# 05_USB7002-PartB.net
KiCad netlist of a schematic drawn in Altium Designer
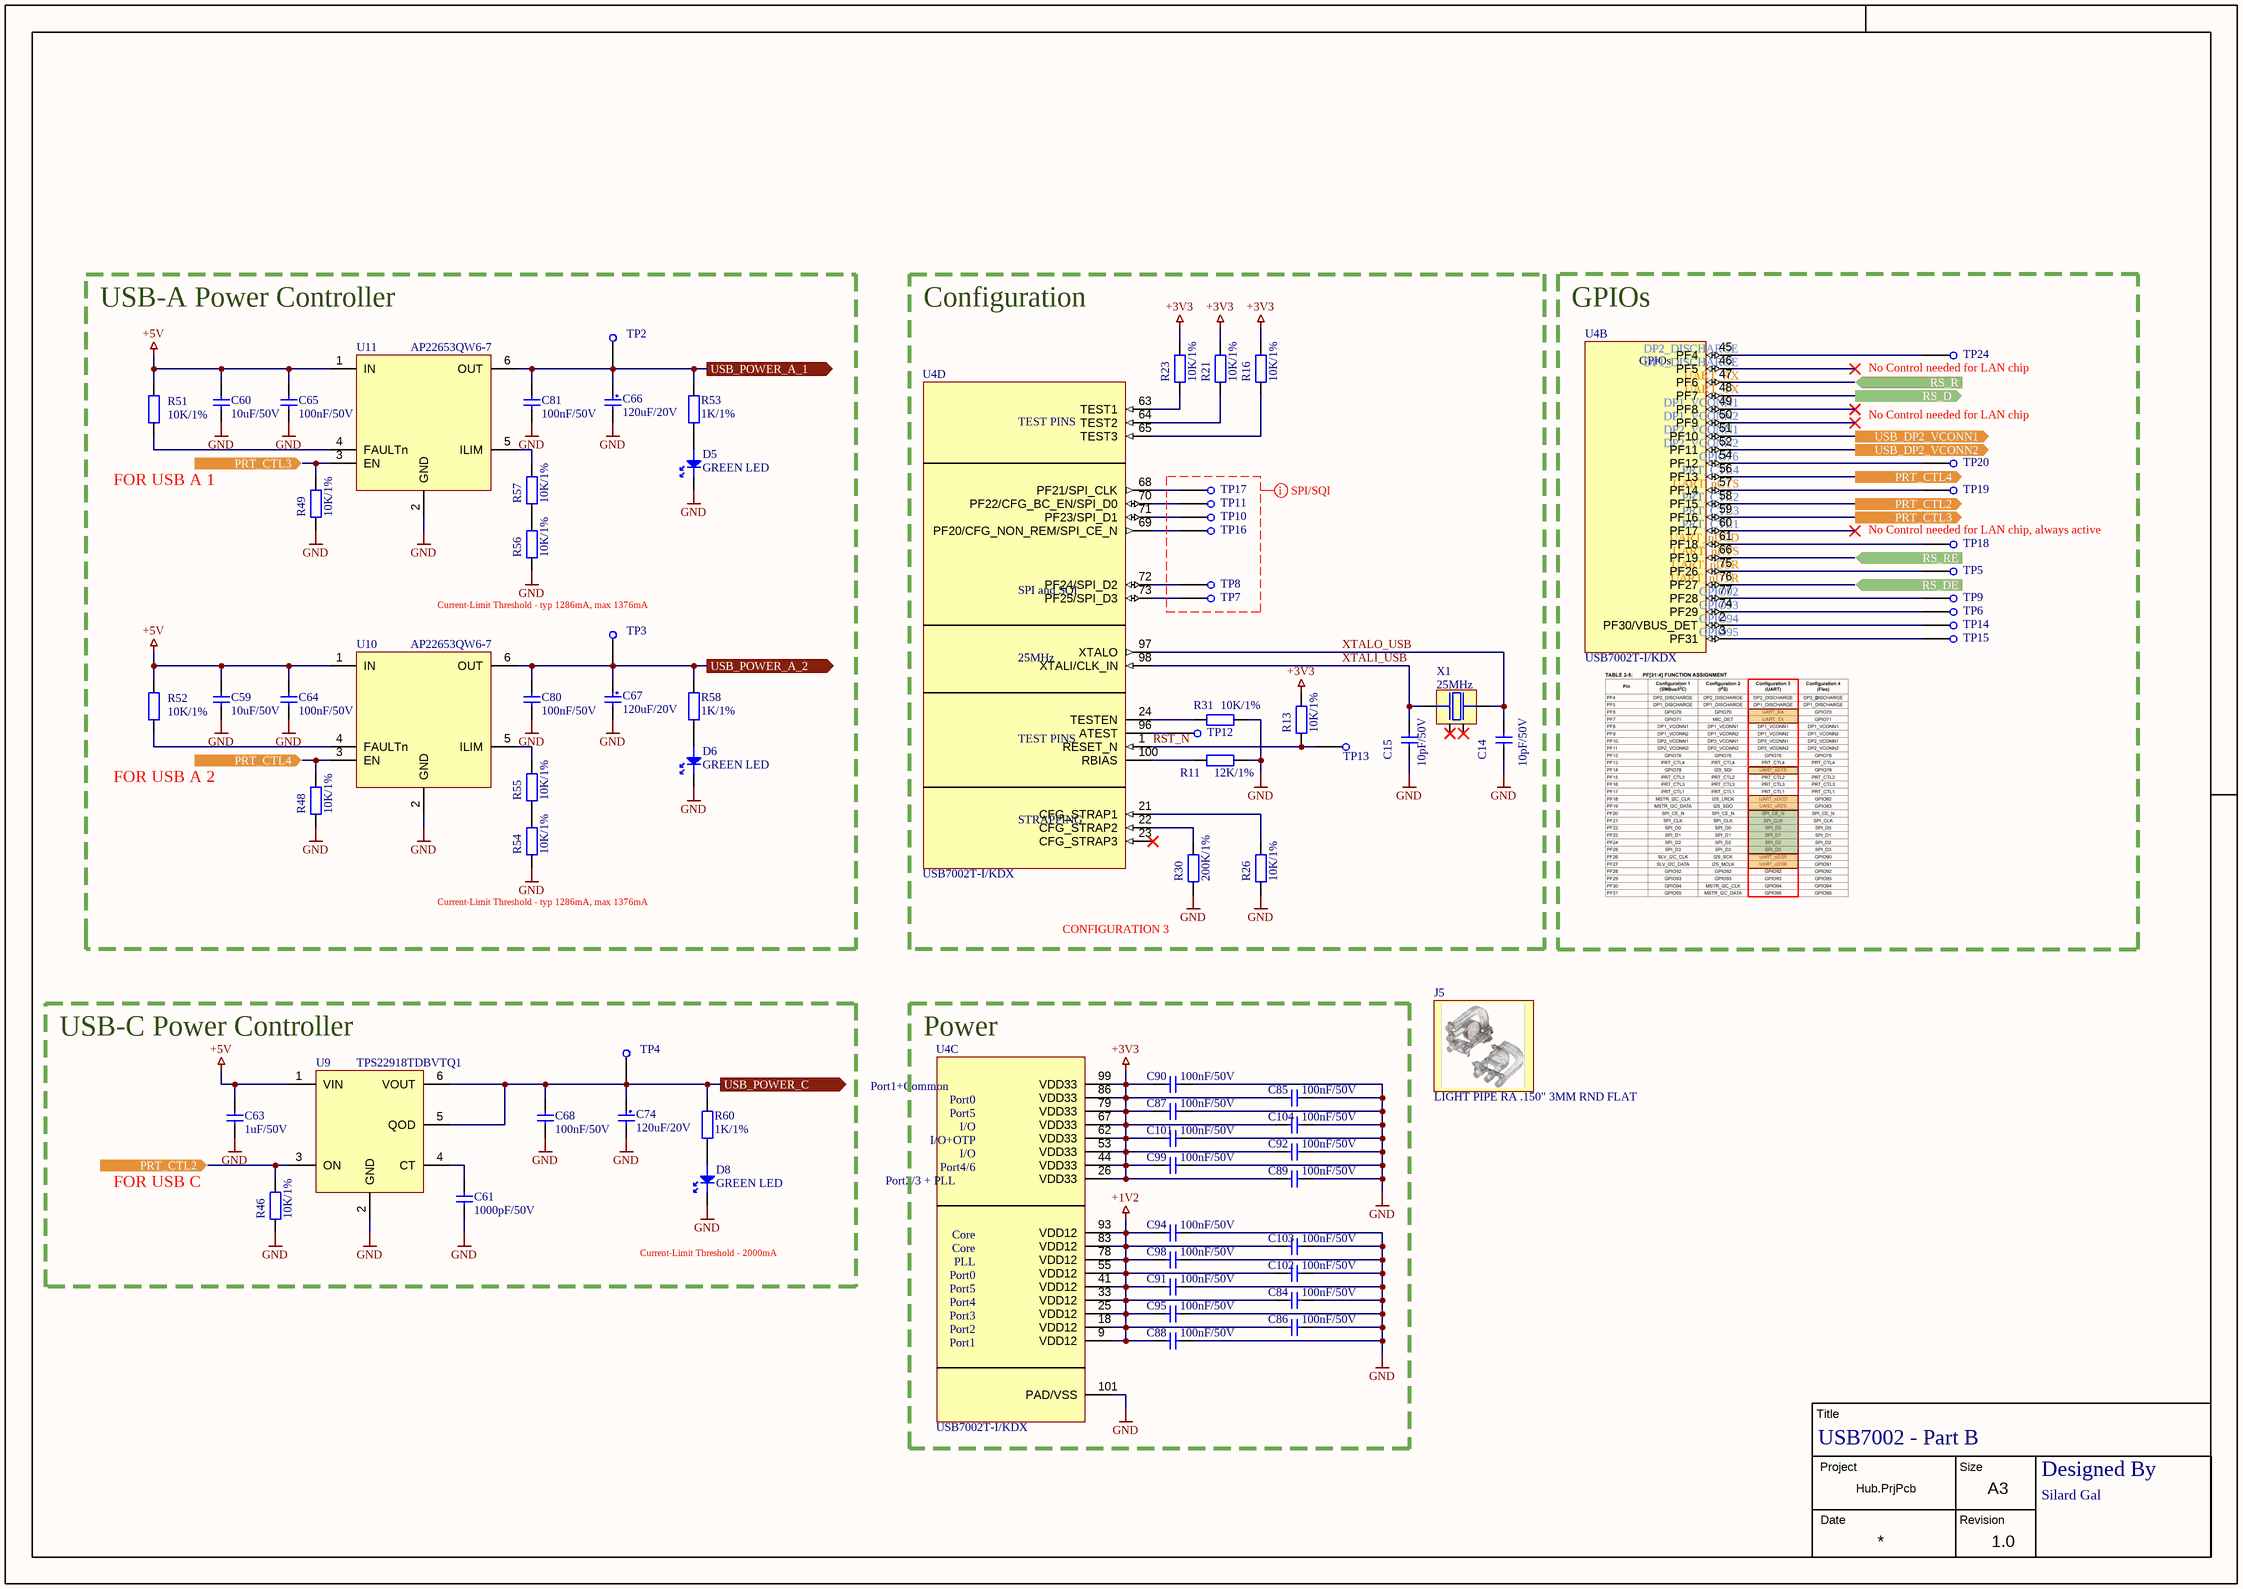
[diagram p0: 05 USB7002-PartB.SchDoc]

(export (version "E")
  (design (tool "Eeschema 10.0.6"))
  (components
    (comp (ref "C14")
      (value "10pF/50V")
      (footprint "CAPC1005X06N")
      (description "10 pF ±5% 50V Ceramic Capacitor C0G, NP0 0402 (1005 Metric)")
      (fields
        (field (name "MANUFACTURER") "Murata Electronics")
        (field (name "MFR_PART_NUMBER") "GCM1555C1H100JA16D")
      )
      (libsource (lib "altium_symbol") (part "GCM1555C1H100JA16D"))
    )
    (comp (ref "C15")
      (value "10pF/50V")
      (footprint "CAPC1005X06N")
      (description "10 pF ±5% 50V Ceramic Capacitor C0G, NP0 0402 (1005 Metric)")
      (fields
        (field (name "MANUFACTURER") "Murata Electronics")
        (field (name "MFR_PART_NUMBER") "GCM1555C1H100JA16D")
      )
      (libsource (lib "altium_symbol") (part "GCM1555C1H100JA16D"))
    )
    (comp (ref "C59")
      (value "10uF/50V")
      (footprint "CAPC3216X18N")
      (description "10 µF ±20% 50V Ceramic Capacitor X5R 1206 (3216 Metric)")
      (fields
        (field (name "MANUFACTURER") "Murata Electronics")
        (field (name "MFR_PART_NUMBER") "GRT31CR61H106ME01L")
      )
      (libsource (lib "altium_symbol") (part "GRT31CR61H106ME01L"))
    )
    (comp (ref "C60")
      (value "10uF/50V")
      (footprint "CAPC3216X18N")
      (description "10 µF ±20% 50V Ceramic Capacitor X5R 1206 (3216 Metric)")
      (fields
        (field (name "MANUFACTURER") "Murata Electronics")
        (field (name "MFR_PART_NUMBER") "GRT31CR61H106ME01L")
      )
      (libsource (lib "altium_symbol") (part "GRT31CR61H106ME01L"))
    )
    (comp (ref "C61")
      (value "1000pF/50V")
      (footprint "CAPC1005X06N")
      (description "1000 pF ±10% 50V Ceramic Capacitor X7R 0402 (1005 Metric)")
      (fields (field (name "MANUFACTURER") "KEMET") (field (name "MFR_PART_NUMBER") "C0402C102K5RECAUTO"))
      (libsource (lib "altium_symbol") (part "C0402C102K5RECAUTO"))
    )
    (comp (ref "C63")
      (value "1uF/50V")
      (footprint "INDC1608X10N")
      (description "1 µF ±10% 50V Ceramic Capacitor X5R 0603 (1608 Metric)")
      (fields
        (field (name "MANUFACTURER") "Murata Electronics")
        (field (name "MFR_PART_NUMBER") "GRT188R61H105KE13D")
      )
      (libsource (lib "altium_symbol") (part "GRT188R61H105KE13D"))
    )
    (comp (ref "C64")
      (value "100nF/50V")
      (footprint "CAPC1005X06N")
      (description "0.1 µF ±10% 50V Ceramic Capacitor X7R 0402 (1005 Metric)")
      (fields
        (field (name "MANUFACTURER") "Murata Electronics")
        (field (name "MFR_PART_NUMBER") "GCM155R71H104KE02J")
      )
      (libsource (lib "altium_symbol") (part "GCM155R71H104KE02J"))
    )
    (comp (ref "C65")
      (value "100nF/50V")
      (footprint "CAPC1005X06N")
      (description "0.1 µF ±10% 50V Ceramic Capacitor X7R 0402 (1005 Metric)")
      (fields
        (field (name "MANUFACTURER") "Murata Electronics")
        (field (name "MFR_PART_NUMBER") "GCM155R71H104KE02J")
      )
      (libsource (lib "altium_symbol") (part "GCM155R71H104KE02J"))
    )
    (comp (ref "C66")
      (value "120uF/20V")
      (footprint "CAPAE7366X60M")
      (description "120 µF 20 V Aluminum - Polymer Capacitors Radial, Can - SMD 34mOhm 2000 Hrs @ 125°C")
      (fields (field (name "MANUFACTURER") "KEMET") (field (name "MFR_PART_NUMBER") "A768EB127M1DLAS034"))
      (libsource (lib "altium_symbol") (part "A768EB127M1DLAS034"))
    )
    (comp (ref "C67")
      (value "120uF/20V")
      (footprint "CAPAE7366X60M")
      (description "120 µF 20 V Aluminum - Polymer Capacitors Radial, Can - SMD 34mOhm 2000 Hrs @ 125°C")
      (fields (field (name "MANUFACTURER") "KEMET") (field (name "MFR_PART_NUMBER") "A768EB127M1DLAS034"))
      (libsource (lib "altium_symbol") (part "A768EB127M1DLAS034"))
    )
    (comp (ref "C68")
      (value "100nF/50V")
      (footprint "CAPC1005X06N")
      (description "0.1 µF ±10% 50V Ceramic Capacitor X7R 0402 (1005 Metric)")
      (fields
        (field (name "MANUFACTURER") "Murata Electronics")
        (field (name "MFR_PART_NUMBER") "GCM155R71H104KE02J")
      )
      (libsource (lib "altium_symbol") (part "GCM155R71H104KE02J"))
    )
    (comp (ref "C74")
      (value "120uF/20V")
      (footprint "CAPAE7366X60M")
      (description "120 µF 20 V Aluminum - Polymer Capacitors Radial, Can - SMD 34mOhm 2000 Hrs @ 125°C")
      (fields (field (name "MANUFACTURER") "KEMET") (field (name "MFR_PART_NUMBER") "A768EB127M1DLAS034"))
      (libsource (lib "altium_symbol") (part "A768EB127M1DLAS034"))
    )
    (comp (ref "C80")
      (value "100nF/50V")
      (footprint "CAPC1005X06N")
      (description "0.1 µF ±10% 50V Ceramic Capacitor X7R 0402 (1005 Metric)")
      (fields
        (field (name "MANUFACTURER") "Murata Electronics")
        (field (name "MFR_PART_NUMBER") "GCM155R71H104KE02J")
      )
      (libsource (lib "altium_symbol") (part "GCM155R71H104KE02J"))
    )
    (comp (ref "C81")
      (value "100nF/50V")
      (footprint "CAPC1005X06N")
      (description "0.1 µF ±10% 50V Ceramic Capacitor X7R 0402 (1005 Metric)")
      (fields
        (field (name "MANUFACTURER") "Murata Electronics")
        (field (name "MFR_PART_NUMBER") "GCM155R71H104KE02J")
      )
      (libsource (lib "altium_symbol") (part "GCM155R71H104KE02J"))
    )
    (comp (ref "C84")
      (value "100nF/50V")
      (footprint "CAPC1005X06N")
      (description "0.1 µF ±10% 50V Ceramic Capacitor X7R 0402 (1005 Metric)")
      (fields
        (field (name "MANUFACTURER") "Murata Electronics")
        (field (name "MFR_PART_NUMBER") "GCM155R71H104KE02J")
      )
      (libsource (lib "altium_symbol") (part "GCM155R71H104KE02J"))
    )
    (comp (ref "C85")
      (value "100nF/50V")
      (footprint "CAPC1005X06N")
      (description "0.1 µF ±10% 50V Ceramic Capacitor X7R 0402 (1005 Metric)")
      (fields
        (field (name "MANUFACTURER") "Murata Electronics")
        (field (name "MFR_PART_NUMBER") "GCM155R71H104KE02J")
      )
      (libsource (lib "altium_symbol") (part "GCM155R71H104KE02J"))
    )
    (comp (ref "C86")
      (value "100nF/50V")
      (footprint "CAPC1005X06N")
      (description "0.1 µF ±10% 50V Ceramic Capacitor X7R 0402 (1005 Metric)")
      (fields
        (field (name "MANUFACTURER") "Murata Electronics")
        (field (name "MFR_PART_NUMBER") "GCM155R71H104KE02J")
      )
      (libsource (lib "altium_symbol") (part "GCM155R71H104KE02J"))
    )
    (comp (ref "C87")
      (value "100nF/50V")
      (footprint "CAPC1005X06N")
      (description "0.1 µF ±10% 50V Ceramic Capacitor X7R 0402 (1005 Metric)")
      (fields
        (field (name "MANUFACTURER") "Murata Electronics")
        (field (name "MFR_PART_NUMBER") "GCM155R71H104KE02J")
      )
      (libsource (lib "altium_symbol") (part "GCM155R71H104KE02J"))
    )
    (comp (ref "C88")
      (value "100nF/50V")
      (footprint "CAPC1005X06N")
      (description "0.1 µF ±10% 50V Ceramic Capacitor X7R 0402 (1005 Metric)")
      (fields
        (field (name "MANUFACTURER") "Murata Electronics")
        (field (name "MFR_PART_NUMBER") "GCM155R71H104KE02J")
      )
      (libsource (lib "altium_symbol") (part "GCM155R71H104KE02J"))
    )
    (comp (ref "C89")
      (value "100nF/50V")
      (footprint "CAPC1005X06N")
      (description "0.1 µF ±10% 50V Ceramic Capacitor X7R 0402 (1005 Metric)")
      (fields
        (field (name "MANUFACTURER") "Murata Electronics")
        (field (name "MFR_PART_NUMBER") "GCM155R71H104KE02J")
      )
      (libsource (lib "altium_symbol") (part "GCM155R71H104KE02J"))
    )
    (comp (ref "C90")
      (value "100nF/50V")
      (footprint "CAPC1005X06N")
      (description "0.1 µF ±10% 50V Ceramic Capacitor X7R 0402 (1005 Metric)")
      (fields
        (field (name "MANUFACTURER") "Murata Electronics")
        (field (name "MFR_PART_NUMBER") "GCM155R71H104KE02J")
      )
      (libsource (lib "altium_symbol") (part "GCM155R71H104KE02J"))
    )
    (comp (ref "C91")
      (value "100nF/50V")
      (footprint "CAPC1005X06N")
      (description "0.1 µF ±10% 50V Ceramic Capacitor X7R 0402 (1005 Metric)")
      (fields
        (field (name "MANUFACTURER") "Murata Electronics")
        (field (name "MFR_PART_NUMBER") "GCM155R71H104KE02J")
      )
      (libsource (lib "altium_symbol") (part "GCM155R71H104KE02J"))
    )
    (comp (ref "C92")
      (value "100nF/50V")
      (footprint "CAPC1005X06N")
      (description "0.1 µF ±10% 50V Ceramic Capacitor X7R 0402 (1005 Metric)")
      (fields
        (field (name "MANUFACTURER") "Murata Electronics")
        (field (name "MFR_PART_NUMBER") "GCM155R71H104KE02J")
      )
      (libsource (lib "altium_symbol") (part "GCM155R71H104KE02J"))
    )
    (comp (ref "C94")
      (value "100nF/50V")
      (footprint "CAPC1005X06N")
      (description "0.1 µF ±10% 50V Ceramic Capacitor X7R 0402 (1005 Metric)")
      (fields
        (field (name "MANUFACTURER") "Murata Electronics")
        (field (name "MFR_PART_NUMBER") "GCM155R71H104KE02J")
      )
      (libsource (lib "altium_symbol") (part "GCM155R71H104KE02J"))
    )
    (comp (ref "C95")
      (value "100nF/50V")
      (footprint "CAPC1005X06N")
      (description "0.1 µF ±10% 50V Ceramic Capacitor X7R 0402 (1005 Metric)")
      (fields
        (field (name "MANUFACTURER") "Murata Electronics")
        (field (name "MFR_PART_NUMBER") "GCM155R71H104KE02J")
      )
      (libsource (lib "altium_symbol") (part "GCM155R71H104KE02J"))
    )
    (comp (ref "C98")
      (value "100nF/50V")
      (footprint "CAPC1005X06N")
      (description "0.1 µF ±10% 50V Ceramic Capacitor X7R 0402 (1005 Metric)")
      (fields
        (field (name "MANUFACTURER") "Murata Electronics")
        (field (name "MFR_PART_NUMBER") "GCM155R71H104KE02J")
      )
      (libsource (lib "altium_symbol") (part "GCM155R71H104KE02J"))
    )
    (comp (ref "C99")
      (value "100nF/50V")
      (footprint "CAPC1005X06N")
      (description "0.1 µF ±10% 50V Ceramic Capacitor X7R 0402 (1005 Metric)")
      (fields
        (field (name "MANUFACTURER") "Murata Electronics")
        (field (name "MFR_PART_NUMBER") "GCM155R71H104KE02J")
      )
      (libsource (lib "altium_symbol") (part "GCM155R71H104KE02J"))
    )
    (comp (ref "C101")
      (value "100nF/50V")
      (footprint "CAPC1005X06N")
      (description "0.1 µF ±10% 50V Ceramic Capacitor X7R 0402 (1005 Metric)")
      (fields
        (field (name "MANUFACTURER") "Murata Electronics")
        (field (name "MFR_PART_NUMBER") "GCM155R71H104KE02J")
      )
      (libsource (lib "altium_symbol") (part "GCM155R71H104KE02J"))
    )
    (comp (ref "C102")
      (value "100nF/50V")
      (footprint "CAPC1005X06N")
      (description "0.1 µF ±10% 50V Ceramic Capacitor X7R 0402 (1005 Metric)")
      (fields
        (field (name "MANUFACTURER") "Murata Electronics")
        (field (name "MFR_PART_NUMBER") "GCM155R71H104KE02J")
      )
      (libsource (lib "altium_symbol") (part "GCM155R71H104KE02J"))
    )
    (comp (ref "C103")
      (value "100nF/50V")
      (footprint "CAPC1005X06N")
      (description "0.1 µF ±10% 50V Ceramic Capacitor X7R 0402 (1005 Metric)")
      (fields
        (field (name "MANUFACTURER") "Murata Electronics")
        (field (name "MFR_PART_NUMBER") "GCM155R71H104KE02J")
      )
      (libsource (lib "altium_symbol") (part "GCM155R71H104KE02J"))
    )
    (comp (ref "C104")
      (value "100nF/50V")
      (footprint "CAPC1005X06N")
      (description "0.1 µF ±10% 50V Ceramic Capacitor X7R 0402 (1005 Metric)")
      (fields
        (field (name "MANUFACTURER") "Murata Electronics")
        (field (name "MFR_PART_NUMBER") "GCM155R71H104KE02J")
      )
      (libsource (lib "altium_symbol") (part "GCM155R71H104KE02J"))
    )
    (comp (ref "D5")
      (value "GREEN LED")
      (footprint "DIOC1608X06L")
      (description "White 0402 Light Emitting Diodes (LED) RoHS")
      (fields (field (name "MANUFACTURER") "Lite-On Inc.") (field (name "MFR_PART_NUMBER") "LTST-C191KGKT"))
      (libsource (lib "altium_symbol") (part "LTST-C191KGKT"))
    )
    (comp (ref "D6")
      (value "GREEN LED")
      (footprint "DIOC1608X06L")
      (description "White 0402 Light Emitting Diodes (LED) RoHS")
      (fields (field (name "MANUFACTURER") "Lite-On Inc.") (field (name "MFR_PART_NUMBER") "LTST-C191KGKT"))
      (libsource (lib "altium_symbol") (part "LTST-C191KGKT"))
    )
    (comp (ref "D8")
      (value "GREEN LED")
      (footprint "DIOC1608X06L")
      (description "White 0402 Light Emitting Diodes (LED) RoHS")
      (fields (field (name "MANUFACTURER") "Lite-On Inc.") (field (name "MFR_PART_NUMBER") "LTST-C191KGKT"))
      (libsource (lib "altium_symbol") (part "LTST-C191KGKT"))
    )
    (comp (ref "J5")
      (value "LIGHT PIPE RA .150\" 3MM RND FLAT")
      (footprint "5151064F")
      (description "Light Pipe 3 High Clear Rigid Board Mount, Press Fit, Right Angle")
      (fields (field (name "MANUFACTURER") "Dialight") (field (name "MFR_PART_NUMBER") "5151064F"))
      (libsource (lib "altium_symbol") (part "5151064F"))
    )
    (comp (ref "R11")
      (value "12K/1%")
      (footprint "RESC1005X04N")
      (description "12 kOhms ±1% 0.1W, 1/10W Chip Resistor 0402 (1005 Metric) Automotive AEC-Q200 Thick Film")
      (fields
        (field (name "MANUFACTURER") "Panasonic Electronic Components")
        (field (name "MFR_PART_NUMBER") "ERJ-2RKF1202X")
      )
      (libsource (lib "altium_symbol") (part "ERJ-2RKF1202X"))
    )
    (comp (ref "R13")
      (value "10K/1%")
      (footprint "RESC1005X04N")
      (description "10 kOhms ±1% 0.063W, 1/16W Chip Resistor 0402 (1005 Metric) Automotive AEC-Q200 Thick Film")
      (fields
        (field (name "MANUFACTURER") "Stackpole Electronics Inc")
        (field (name "MFR_PART_NUMBER") "RMCF0402FT10K0")
      )
      (libsource (lib "altium_symbol") (part "RMCF0402FT10K0"))
    )
    (comp (ref "R16")
      (value "10K/1%")
      (footprint "RESC1005X04N")
      (description "10 kOhms ±1% 0.063W, 1/16W Chip Resistor 0402 (1005 Metric) Automotive AEC-Q200 Thick Film")
      (fields
        (field (name "MANUFACTURER") "Stackpole Electronics Inc")
        (field (name "MFR_PART_NUMBER") "RMCF0402FT10K0")
      )
      (libsource (lib "altium_symbol") (part "RMCF0402FT10K0"))
    )
    (comp (ref "R21")
      (value "10K/1%")
      (footprint "RESC1005X04N")
      (description "10 kOhms ±1% 0.063W, 1/16W Chip Resistor 0402 (1005 Metric) Automotive AEC-Q200 Thick Film")
      (fields
        (field (name "MANUFACTURER") "Stackpole Electronics Inc")
        (field (name "MFR_PART_NUMBER") "RMCF0402FT10K0")
      )
      (libsource (lib "altium_symbol") (part "RMCF0402FT10K0"))
    )
    (comp (ref "R23")
      (value "10K/1%")
      (footprint "RESC1005X04N")
      (description "10 kOhms ±1% 0.063W, 1/16W Chip Resistor 0402 (1005 Metric) Automotive AEC-Q200 Thick Film")
      (fields
        (field (name "MANUFACTURER") "Stackpole Electronics Inc")
        (field (name "MFR_PART_NUMBER") "RMCF0402FT10K0")
      )
      (libsource (lib "altium_symbol") (part "RMCF0402FT10K0"))
    )
    (comp (ref "R26")
      (value "10K/1%")
      (footprint "RESC1005X04N")
      (description "10 kOhms ±1% 0.063W, 1/16W Chip Resistor 0402 (1005 Metric) Automotive AEC-Q200 Thick Film")
      (fields
        (field (name "MANUFACTURER") "Stackpole Electronics Inc")
        (field (name "MFR_PART_NUMBER") "RMCF0402FT10K0")
      )
      (libsource (lib "altium_symbol") (part "RMCF0402FT10K0"))
    )
    (comp (ref "R30")
      (value "200K/1%")
      (footprint "RESC1005X04N")
      (description "200 kOhms ±1% 0.063W, 1/16W Chip Resistor 0402 (1005 Metric) Automotive AEC-Q200 Thick Film")
      (fields
        (field (name "MANUFACTURER") "Stackpole Electronics Inc")
        (field (name "MFR_PART_NUMBER") "RMCF0402FT200K")
      )
      (libsource (lib "altium_symbol") (part "RMCF0402FT200K"))
    )
    (comp (ref "R31")
      (value "10K/1%")
      (footprint "RESC1005X04N")
      (description "10 kOhms ±1% 0.063W, 1/16W Chip Resistor 0402 (1005 Metric) Automotive AEC-Q200 Thick Film")
      (fields
        (field (name "MANUFACTURER") "Stackpole Electronics Inc")
        (field (name "MFR_PART_NUMBER") "RMCF0402FT10K0")
      )
      (libsource (lib "altium_symbol") (part "RMCF0402FT10K0"))
    )
    (comp (ref "R46")
      (value "10K/1%")
      (footprint "RESC1005X04N")
      (description "10 kOhms ±1% 0.063W, 1/16W Chip Resistor 0402 (1005 Metric) Automotive AEC-Q200 Thick Film")
      (fields
        (field (name "MANUFACTURER") "Stackpole Electronics Inc")
        (field (name "MFR_PART_NUMBER") "RMCF0402FT10K0")
      )
      (libsource (lib "altium_symbol") (part "RMCF0402FT10K0"))
    )
    (comp (ref "R48")
      (value "10K/1%")
      (footprint "RESC1005X04N")
      (description "10 kOhms ±1% 0.063W, 1/16W Chip Resistor 0402 (1005 Metric) Automotive AEC-Q200 Thick Film")
      (fields
        (field (name "MANUFACTURER") "Stackpole Electronics Inc")
        (field (name "MFR_PART_NUMBER") "RMCF0402FT10K0")
      )
      (libsource (lib "altium_symbol") (part "RMCF0402FT10K0"))
    )
    (comp (ref "R49")
      (value "10K/1%")
      (footprint "RESC1005X04N")
      (description "10 kOhms ±1% 0.063W, 1/16W Chip Resistor 0402 (1005 Metric) Automotive AEC-Q200 Thick Film")
      (fields
        (field (name "MANUFACTURER") "Stackpole Electronics Inc")
        (field (name "MFR_PART_NUMBER") "RMCF0402FT10K0")
      )
      (libsource (lib "altium_symbol") (part "RMCF0402FT10K0"))
    )
    (comp (ref "R51")
      (value "10K/1%")
      (footprint "RESC1005X04N")
      (description "10 kOhms ±1% 0.063W, 1/16W Chip Resistor 0402 (1005 Metric) Automotive AEC-Q200 Thick Film")
      (fields
        (field (name "MANUFACTURER") "Stackpole Electronics Inc")
        (field (name "MFR_PART_NUMBER") "RMCF0402FT10K0")
      )
      (libsource (lib "altium_symbol") (part "RMCF0402FT10K0"))
    )
    (comp (ref "R52")
      (value "10K/1%")
      (footprint "RESC1005X04N")
      (description "10 kOhms ±1% 0.063W, 1/16W Chip Resistor 0402 (1005 Metric) Automotive AEC-Q200 Thick Film")
      (fields
        (field (name "MANUFACTURER") "Stackpole Electronics Inc")
        (field (name "MFR_PART_NUMBER") "RMCF0402FT10K0")
      )
      (libsource (lib "altium_symbol") (part "RMCF0402FT10K0"))
    )
    (comp (ref "R53")
      (value "1K/1%")
      (footprint "RESC1005X04N")
      (description "1 kOhms ±1% 0.063W, 1/16W Chip Resistor 0402 (1005 Metric) Automotive AEC-Q200 Thick Film")
      (fields
        (field (name "MANUFACTURER") "Stackpole Electronics Inc")
        (field (name "MFR_PART_NUMBER") "RMCF0402FT1K00")
      )
      (libsource (lib "altium_symbol") (part "RMCF0402FT1K00"))
    )
    (comp (ref "R54")
      (value "10K/1%")
      (footprint "RESC1005X04N")
      (description "10 kOhms ±1% 0.063W, 1/16W Chip Resistor 0402 (1005 Metric) Automotive AEC-Q200 Thick Film")
      (fields
        (field (name "MANUFACTURER") "Stackpole Electronics Inc")
        (field (name "MFR_PART_NUMBER") "RMCF0402FT10K0")
      )
      (libsource (lib "altium_symbol") (part "RMCF0402FT10K0"))
    )
    (comp (ref "R55")
      (value "10K/1%")
      (footprint "RESC1005X04N")
      (description "10 kOhms ±1% 0.063W, 1/16W Chip Resistor 0402 (1005 Metric) Automotive AEC-Q200 Thick Film")
      (fields
        (field (name "MANUFACTURER") "Stackpole Electronics Inc")
        (field (name "MFR_PART_NUMBER") "RMCF0402FT10K0")
      )
      (libsource (lib "altium_symbol") (part "RMCF0402FT10K0"))
    )
    (comp (ref "R56")
      (value "10K/1%")
      (footprint "RESC1005X04N")
      (description "10 kOhms ±1% 0.063W, 1/16W Chip Resistor 0402 (1005 Metric) Automotive AEC-Q200 Thick Film")
      (fields
        (field (name "MANUFACTURER") "Stackpole Electronics Inc")
        (field (name "MFR_PART_NUMBER") "RMCF0402FT10K0")
      )
      (libsource (lib "altium_symbol") (part "RMCF0402FT10K0"))
    )
    (comp (ref "R57")
      (value "10K/1%")
      (footprint "RESC1005X04N")
      (description "10 kOhms ±1% 0.063W, 1/16W Chip Resistor 0402 (1005 Metric) Automotive AEC-Q200 Thick Film")
      (fields
        (field (name "MANUFACTURER") "Stackpole Electronics Inc")
        (field (name "MFR_PART_NUMBER") "RMCF0402FT10K0")
      )
      (libsource (lib "altium_symbol") (part "RMCF0402FT10K0"))
    )
    (comp (ref "R58")
      (value "1K/1%")
      (footprint "RESC1005X04N")
      (description "1 kOhms ±1% 0.063W, 1/16W Chip Resistor 0402 (1005 Metric) Automotive AEC-Q200 Thick Film")
      (fields
        (field (name "MANUFACTURER") "Stackpole Electronics Inc")
        (field (name "MFR_PART_NUMBER") "RMCF0402FT1K00")
      )
      (libsource (lib "altium_symbol") (part "RMCF0402FT1K00"))
    )
    (comp (ref "R60")
      (value "1K/1%")
      (footprint "RESC1005X04N")
      (description "1 kOhms ±1% 0.063W, 1/16W Chip Resistor 0402 (1005 Metric) Automotive AEC-Q200 Thick Film")
      (fields
        (field (name "MANUFACTURER") "Stackpole Electronics Inc")
        (field (name "MFR_PART_NUMBER") "RMCF0402FT1K00")
      )
      (libsource (lib "altium_symbol") (part "RMCF0402FT1K00"))
    )
    (comp (ref "TP2")
      (value "Test Point 1mm")
      (footprint "TEST_POINT_1mm")
      (libsource (lib "altium_symbol") (part "TestPoint"))
    )
    (comp (ref "TP3")
      (value "Test Point 1mm")
      (footprint "TEST_POINT_1mm")
      (libsource (lib "altium_symbol") (part "TestPoint"))
    )
    (comp (ref "TP4")
      (value "Test Point 1mm")
      (footprint "TEST_POINT_1mm")
      (libsource (lib "altium_symbol") (part "TestPoint"))
    )
    (comp (ref "TP5")
      (value "Test Point 1mm")
      (footprint "TEST_POINT_1mm")
      (libsource (lib "altium_symbol") (part "TestPoint"))
    )
    (comp (ref "TP6")
      (value "Test Point 1mm")
      (footprint "TEST_POINT_1mm")
      (libsource (lib "altium_symbol") (part "TestPoint"))
    )
    (comp (ref "TP7")
      (value "Test Point 1mm")
      (footprint "TEST_POINT_1mm")
      (libsource (lib "altium_symbol") (part "TestPoint"))
    )
    (comp (ref "TP8")
      (value "Test Point 1mm")
      (footprint "TEST_POINT_1mm")
      (libsource (lib "altium_symbol") (part "TestPoint"))
    )
    (comp (ref "TP9")
      (value "Test Point 1mm")
      (footprint "TEST_POINT_1mm")
      (libsource (lib "altium_symbol") (part "TestPoint"))
    )
    (comp (ref "TP10")
      (value "Test Point 1mm")
      (footprint "TEST_POINT_1mm")
      (libsource (lib "altium_symbol") (part "TestPoint"))
    )
    (comp (ref "TP11")
      (value "Test Point 1mm")
      (footprint "TEST_POINT_1mm")
      (libsource (lib "altium_symbol") (part "TestPoint"))
    )
    (comp (ref "TP12")
      (value "Test Point 1mm")
      (footprint "TEST_POINT_1mm")
      (libsource (lib "altium_symbol") (part "TestPoint"))
    )
    (comp (ref "TP13")
      (value "Test Point 1mm")
      (footprint "TEST_POINT_1mm")
      (libsource (lib "altium_symbol") (part "TestPoint"))
    )
    (comp (ref "TP14")
      (value "Test Point 1mm")
      (footprint "TEST_POINT_1mm")
      (libsource (lib "altium_symbol") (part "TestPoint"))
    )
    (comp (ref "TP15")
      (value "Test Point 1mm")
      (footprint "TEST_POINT_1mm")
      (libsource (lib "altium_symbol") (part "TestPoint"))
    )
    (comp (ref "TP16")
      (value "Test Point 1mm")
      (footprint "TEST_POINT_1mm")
      (libsource (lib "altium_symbol") (part "TestPoint"))
    )
    (comp (ref "TP17")
      (value "Test Point 1mm")
      (footprint "TEST_POINT_1mm")
      (libsource (lib "altium_symbol") (part "TestPoint"))
    )
    (comp (ref "TP18")
      (value "Test Point 1mm")
      (footprint "TEST_POINT_1mm")
      (libsource (lib "altium_symbol") (part "TestPoint"))
    )
    (comp (ref "TP19")
      (value "Test Point 1mm")
      (footprint "TEST_POINT_1mm")
      (libsource (lib "altium_symbol") (part "TestPoint"))
    )
    (comp (ref "TP20")
      (value "Test Point 1mm")
      (footprint "TEST_POINT_1mm")
      (libsource (lib "altium_symbol") (part "TestPoint"))
    )
    (comp (ref "TP24")
      (value "Test Point 1mm")
      (footprint "TEST_POINT_1mm")
      (libsource (lib "altium_symbol") (part "TestPoint"))
    )
    (comp (ref "U4")
      (value "USB7002T-I/KDX")
      (footprint "QFN40P1200X1200X90_HS-101N")
      (description "USB Hub Controller USB 3.1 USB Interface 100-VQFN (12x12)")
      (fields (field (name "MANUFACTURER") "Microchip Technology"))
      (libsource (lib "altium_symbol") (part "USB7002T-I/KDX"))
    )
    (comp (ref "U9")
      (value "TPS22918TDBVTQ1")
      (footprint "SOT95P280X145-6N")
      (description "Power Switch/Driver 1:1 N-Channel 2A SOT-23-6")
      (fields (field (name "MANUFACTURER") "Texas Instruments"))
      (libsource (lib "altium_symbol") (part "TPS22918TDBVTQ1"))
    )
    (comp (ref "U10")
      (value "AP22653QW6-7")
      (footprint "SOT95P280X145-6N-1")
      (description "Power Switch/Driver 1:1 N-Channel 1.2A SOT-26 (Type A1)")
      (fields (field (name "MANUFACTURER") "Diodes Incorporated"))
      (libsource (lib "altium_symbol") (part "AP22653QW6-7"))
    )
    (comp (ref "U11")
      (value "AP22653QW6-7")
      (footprint "SOT95P280X145-6N-1")
      (description "Power Switch/Driver 1:1 N-Channel 1.2A SOT-26 (Type A1)")
      (fields (field (name "MANUFACTURER") "Diodes Incorporated"))
      (libsource (lib "altium_symbol") (part "AP22653QW6-7"))
    )
    (comp (ref "X1")
      (value "25MHz")
      (footprint "XRCGB25M000F3M00R0")
      (description "25 MHz ±30ppm Crystal 6pF 150 Ohms 4-SMD, No Lead")
      (fields
        (field (name "MANUFACTURER") "Murata Electronics")
        (field (name "MFR_PART_NUMBER") "XRCGB25M000F3M00R0")
      )
      (libsource (lib "altium_symbol") (part "XRCGB25M000F3M00R0"))
    )
  )
  (nets
    (net (code "1") (name "+1V2") (class "Default")
      (node (ref "C102") (pin "2") (pinfunction "2_2") (pintype "passive"))
      (node (ref "C103") (pin "2") (pinfunction "2_2") (pintype "passive"))
      (node (ref "C84") (pin "2") (pinfunction "2_2") (pintype "passive"))
      (node (ref "C86") (pin "2") (pinfunction "2_2") (pintype "passive"))
      (node (ref "C88") (pin "2") (pinfunction "2_2") (pintype "passive"))
      (node (ref "C91") (pin "2") (pinfunction "2_2") (pintype "passive"))
      (node (ref "C94") (pin "2") (pinfunction "2_2") (pintype "passive"))
      (node (ref "C95") (pin "2") (pinfunction "2_2") (pintype "passive"))
      (node (ref "C98") (pin "2") (pinfunction "2_2") (pintype "passive"))
      (node (ref "U4") (pin "18") (pinfunction "VDD12_18") (pintype "power_in"))
      (node (ref "U4") (pin "25") (pinfunction "VDD12_25") (pintype "power_in"))
      (node (ref "U4") (pin "33") (pinfunction "VDD12_33") (pintype "power_in"))
      (node (ref "U4") (pin "41") (pinfunction "VDD12_41") (pintype "power_in"))
      (node (ref "U4") (pin "55") (pinfunction "VDD12_55") (pintype "power_in"))
      (node (ref "U4") (pin "78") (pinfunction "VDD12_78") (pintype "power_in"))
      (node (ref "U4") (pin "83") (pinfunction "VDD12_83") (pintype "power_in"))
      (node (ref "U4") (pin "9") (pinfunction "VDD12_9") (pintype "power_in"))
      (node (ref "U4") (pin "93") (pinfunction "VDD12_93") (pintype "power_in"))
    )
    (net (code "2") (name "+3V3") (class "Default")
      (node (ref "C101") (pin "2") (pinfunction "2_2") (pintype "passive"))
      (node (ref "C104") (pin "2") (pinfunction "2_2") (pintype "passive"))
      (node (ref "C85") (pin "2") (pinfunction "2_2") (pintype "passive"))
      (node (ref "C87") (pin "2") (pinfunction "2_2") (pintype "passive"))
      (node (ref "C89") (pin "2") (pinfunction "2_2") (pintype "passive"))
      (node (ref "C90") (pin "2") (pinfunction "2_2") (pintype "passive"))
      (node (ref "C92") (pin "2") (pinfunction "2_2") (pintype "passive"))
      (node (ref "C99") (pin "2") (pinfunction "2_2") (pintype "passive"))
      (node (ref "R13") (pin "1") (pinfunction "1_1") (pintype "passive"))
      (node (ref "R16") (pin "1") (pinfunction "1_1") (pintype "passive"))
      (node (ref "R21") (pin "1") (pinfunction "1_1") (pintype "passive"))
      (node (ref "R23") (pin "1") (pinfunction "1_1") (pintype "passive"))
      (node (ref "U4") (pin "26") (pinfunction "VDD33_26") (pintype "power_in"))
      (node (ref "U4") (pin "44") (pinfunction "VDD33_44") (pintype "power_in"))
      (node (ref "U4") (pin "53") (pinfunction "VDD33_53") (pintype "power_in"))
      (node (ref "U4") (pin "62") (pinfunction "VDD33_62") (pintype "power_in"))
      (node (ref "U4") (pin "67") (pinfunction "VDD33_67") (pintype "power_in"))
      (node (ref "U4") (pin "79") (pinfunction "VDD33_79") (pintype "power_in"))
      (node (ref "U4") (pin "86") (pinfunction "VDD33_86") (pintype "power_in"))
      (node (ref "U4") (pin "99") (pinfunction "VDD33_99") (pintype "power_in"))
    )
    (net (code "3") (name "+5V") (class "Default")
      (node (ref "C59") (pin "2") (pinfunction "2_2") (pintype "passive"))
      (node (ref "C60") (pin "2") (pinfunction "2_2") (pintype "passive"))
      (node (ref "C63") (pin "2") (pinfunction "2_2") (pintype "passive"))
      (node (ref "C64") (pin "1") (pinfunction "1_1") (pintype "passive"))
      (node (ref "C65") (pin "1") (pinfunction "1_1") (pintype "passive"))
      (node (ref "R51") (pin "1") (pinfunction "1_1") (pintype "passive"))
      (node (ref "R52") (pin "1") (pinfunction "1_1") (pintype "passive"))
      (node (ref "U10") (pin "1") (pinfunction "IN_1") (pintype "passive"))
      (node (ref "U11") (pin "1") (pinfunction "IN_1") (pintype "passive"))
      (node (ref "U9") (pin "1") (pinfunction "VIN_1") (pintype "passive"))
    )
    (net (code "4") (name "/PRT_CTL2") (class "Default")
      (node (ref "R46") (pin "1") (pinfunction "1_1") (pintype "passive"))
      (node (ref "U4") (pin "58") (pinfunction "PF15_58") (pintype "bidirectional"))
      (node (ref "U9") (pin "3") (pinfunction "ON_3") (pintype "passive"))
    )
    (net (code "5") (name "/PRT_CTL3") (class "Default")
      (node (ref "R49") (pin "1") (pinfunction "1_1") (pintype "passive"))
      (node (ref "U11") (pin "3") (pinfunction "EN_3") (pintype "passive"))
      (node (ref "U4") (pin "59") (pinfunction "PF16_59") (pintype "bidirectional"))
    )
    (net (code "6") (name "/PRT_CTL4") (class "Default")
      (node (ref "R48") (pin "1") (pinfunction "1_1") (pintype "passive"))
      (node (ref "U10") (pin "3") (pinfunction "EN_3") (pintype "passive"))
      (node (ref "U4") (pin "56") (pinfunction "PF13_56") (pintype "bidirectional"))
    )
    (net (code "7") (name "/RST_N") (class "Default")
      (node (ref "R13") (pin "2") (pinfunction "2_2") (pintype "passive"))
      (node (ref "TP13") (pin "1") (pinfunction "1_1") (pintype "passive"))
      (node (ref "U4") (pin "1") (pinfunction "RESET_N_1") (pintype "input"))
    )
    (net (code "8") (name "/RS_D") (class "Default")
      (node (ref "U4") (pin "48") (pinfunction "PF7_48") (pintype "bidirectional"))
    )
    (net (code "9") (name "/RS_DE") (class "Default")
      (node (ref "U4") (pin "76") (pinfunction "PF27_76") (pintype "bidirectional"))
    )
    (net (code "10") (name "/RS_R") (class "Default")
      (node (ref "U4") (pin "47") (pinfunction "PF6_47") (pintype "bidirectional"))
    )
    (net (code "11") (name "/RS_RE") (class "Default")
      (node (ref "U4") (pin "66") (pinfunction "PF19_66") (pintype "bidirectional"))
    )
    (net (code "12") (name "/USB_DP2_VCONN1") (class "Default")
      (node (ref "U4") (pin "51") (pinfunction "PF10_51") (pintype "bidirectional"))
    )
    (net (code "13") (name "/USB_DP2_VCONN2") (class "Default")
      (node (ref "U4") (pin "52") (pinfunction "PF11_52") (pintype "bidirectional"))
    )
    (net (code "14") (name "/USB_POWER_A_1") (class "Default")
      (node (ref "C66") (pin "1") (pinfunction "1_1") (pintype "passive"))
      (node (ref "C81") (pin "1") (pinfunction "1_1") (pintype "passive"))
      (node (ref "R53") (pin "2") (pinfunction "2_2") (pintype "passive"))
      (node (ref "TP2") (pin "1") (pinfunction "1_1") (pintype "passive"))
      (node (ref "U11") (pin "6") (pinfunction "OUT_6") (pintype "passive"))
    )
    (net (code "15") (name "/USB_POWER_A_2") (class "Default")
      (node (ref "C67") (pin "1") (pinfunction "1_1") (pintype "passive"))
      (node (ref "C80") (pin "1") (pinfunction "1_1") (pintype "passive"))
      (node (ref "R58") (pin "2") (pinfunction "2_2") (pintype "passive"))
      (node (ref "TP3") (pin "1") (pinfunction "1_1") (pintype "passive"))
      (node (ref "U10") (pin "6") (pinfunction "OUT_6") (pintype "passive"))
    )
    (net (code "16") (name "/USB_POWER_C") (class "Default")
      (node (ref "C68") (pin "1") (pinfunction "1_1") (pintype "passive"))
      (node (ref "C74") (pin "1") (pinfunction "1_1") (pintype "passive"))
      (node (ref "R60") (pin "2") (pinfunction "2_2") (pintype "passive"))
      (node (ref "TP4") (pin "1") (pinfunction "1_1") (pintype "passive"))
      (node (ref "U9") (pin "5") (pinfunction "QOD_5") (pintype "passive"))
      (node (ref "U9") (pin "6") (pinfunction "VOUT_6") (pintype "passive"))
    )
    (net (code "17") (name "/XTALI_USB") (class "Default")
      (node (ref "C15") (pin "2") (pinfunction "2_2") (pintype "passive"))
      (node (ref "U4") (pin "98") (pinfunction "XTALI/CLK_IN_98") (pintype "input"))
      (node (ref "X1") (pin "1") (pinfunction "1_1") (pintype "passive"))
    )
    (net (code "18") (name "/XTALO_USB") (class "Default")
      (node (ref "C14") (pin "2") (pinfunction "2_2") (pintype "passive"))
      (node (ref "U4") (pin "97") (pinfunction "XTALO_97") (pintype "output"))
      (node (ref "X1") (pin "3") (pinfunction "3_3") (pintype "passive"))
    )
    (net (code "19") (name "GND") (class "Default")
      (node (ref "C101") (pin "1") (pinfunction "1_1") (pintype "passive"))
      (node (ref "C102") (pin "1") (pinfunction "1_1") (pintype "passive"))
      (node (ref "C103") (pin "1") (pinfunction "1_1") (pintype "passive"))
      (node (ref "C104") (pin "1") (pinfunction "1_1") (pintype "passive"))
      (node (ref "C14") (pin "1") (pinfunction "1_1") (pintype "passive"))
      (node (ref "C15") (pin "1") (pinfunction "1_1") (pintype "passive"))
      (node (ref "C59") (pin "1") (pinfunction "1_1") (pintype "passive"))
      (node (ref "C60") (pin "1") (pinfunction "1_1") (pintype "passive"))
      (node (ref "C61") (pin "1") (pinfunction "1_1") (pintype "passive"))
      (node (ref "C63") (pin "1") (pinfunction "1_1") (pintype "passive"))
      (node (ref "C64") (pin "2") (pinfunction "2_2") (pintype "passive"))
      (node (ref "C65") (pin "2") (pinfunction "2_2") (pintype "passive"))
      (node (ref "C66") (pin "2") (pinfunction "2_2") (pintype "passive"))
      (node (ref "C67") (pin "2") (pinfunction "2_2") (pintype "passive"))
      (node (ref "C68") (pin "2") (pinfunction "2_2") (pintype "passive"))
      (node (ref "C74") (pin "2") (pinfunction "2_2") (pintype "passive"))
      (node (ref "C80") (pin "2") (pinfunction "2_2") (pintype "passive"))
      (node (ref "C81") (pin "2") (pinfunction "2_2") (pintype "passive"))
      (node (ref "C84") (pin "1") (pinfunction "1_1") (pintype "passive"))
      (node (ref "C85") (pin "1") (pinfunction "1_1") (pintype "passive"))
      (node (ref "C86") (pin "1") (pinfunction "1_1") (pintype "passive"))
      (node (ref "C87") (pin "1") (pinfunction "1_1") (pintype "passive"))
      (node (ref "C88") (pin "1") (pinfunction "1_1") (pintype "passive"))
      (node (ref "C89") (pin "1") (pinfunction "1_1") (pintype "passive"))
      (node (ref "C90") (pin "1") (pinfunction "1_1") (pintype "passive"))
      (node (ref "C91") (pin "1") (pinfunction "1_1") (pintype "passive"))
      (node (ref "C92") (pin "1") (pinfunction "1_1") (pintype "passive"))
      (node (ref "C94") (pin "1") (pinfunction "1_1") (pintype "passive"))
      (node (ref "C95") (pin "1") (pinfunction "1_1") (pintype "passive"))
      (node (ref "C98") (pin "1") (pinfunction "1_1") (pintype "passive"))
      (node (ref "C99") (pin "1") (pinfunction "1_1") (pintype "passive"))
      (node (ref "D5") (pin "1") (pinfunction "1_1") (pintype "passive"))
      (node (ref "D6") (pin "1") (pinfunction "1_1") (pintype "passive"))
      (node (ref "D8") (pin "1") (pinfunction "1_1") (pintype "passive"))
      (node (ref "R11") (pin "1") (pinfunction "1_1") (pintype "passive"))
      (node (ref "R26") (pin "2") (pinfunction "2_2") (pintype "passive"))
      (node (ref "R30") (pin "1") (pinfunction "1_1") (pintype "passive"))
      (node (ref "R31") (pin "1") (pinfunction "1_1") (pintype "passive"))
      (node (ref "R46") (pin "2") (pinfunction "2_2") (pintype "passive"))
      (node (ref "R48") (pin "2") (pinfunction "2_2") (pintype "passive"))
      (node (ref "R49") (pin "2") (pinfunction "2_2") (pintype "passive"))
      (node (ref "R54") (pin "2") (pinfunction "2_2") (pintype "passive"))
      (node (ref "R56") (pin "2") (pinfunction "2_2") (pintype "passive"))
      (node (ref "U10") (pin "2") (pinfunction "GND_2") (pintype "passive"))
      (node (ref "U11") (pin "2") (pinfunction "GND_2") (pintype "passive"))
      (node (ref "U4") (pin "101") (pinfunction "PAD/VSS_101") (pintype "power_in"))
      (node (ref "U9") (pin "2") (pinfunction "GND_2") (pintype "passive"))
    )
    (net (code "20") (name "Net-(D5-Pad2)") (class "Default")
      (node (ref "D5") (pin "2") (pinfunction "2_2") (pintype "passive"))
      (node (ref "R53") (pin "1") (pinfunction "1_1") (pintype "passive"))
    )
    (net (code "21") (name "Net-(D6-Pad2)") (class "Default")
      (node (ref "D6") (pin "2") (pinfunction "2_2") (pintype "passive"))
      (node (ref "R58") (pin "1") (pinfunction "1_1") (pintype "passive"))
    )
    (net (code "22") (name "Net-(D8-Pad2)") (class "Default")
      (node (ref "D8") (pin "2") (pinfunction "2_2") (pintype "passive"))
      (node (ref "R60") (pin "1") (pinfunction "1_1") (pintype "passive"))
    )
    (net (code "23") (name "Net-(R54-Pad1)") (class "Default")
      (node (ref "R54") (pin "1") (pinfunction "1_1") (pintype "passive"))
      (node (ref "R55") (pin "2") (pinfunction "2_2") (pintype "passive"))
    )
    (net (code "24") (name "Net-(R56-Pad1)") (class "Default")
      (node (ref "R56") (pin "1") (pinfunction "1_1") (pintype "passive"))
      (node (ref "R57") (pin "2") (pinfunction "2_2") (pintype "passive"))
    )
    (net (code "25") (name "Net-(U4B-PF4)") (class "Default")
      (node (ref "TP24") (pin "1") (pinfunction "1_1") (pintype "passive"))
      (node (ref "U4") (pin "45") (pinfunction "PF4_45") (pintype "bidirectional"))
    )
    (net (code "26") (name "Net-(U4B-PF12)") (class "Default")
      (node (ref "TP20") (pin "1") (pinfunction "1_1") (pintype "passive"))
      (node (ref "U4") (pin "54") (pinfunction "PF12_54") (pintype "bidirectional"))
    )
    (net (code "27") (name "Net-(U4B-PF14)") (class "Default")
      (node (ref "TP19") (pin "1") (pinfunction "1_1") (pintype "passive"))
      (node (ref "U4") (pin "57") (pinfunction "PF14_57") (pintype "bidirectional"))
    )
    (net (code "28") (name "Net-(U4B-PF18)") (class "Default")
      (node (ref "TP18") (pin "1") (pinfunction "1_1") (pintype "passive"))
      (node (ref "U4") (pin "61") (pinfunction "PF18_61") (pintype "bidirectional"))
    )
    (net (code "29") (name "Net-(U4B-PF26)") (class "Default")
      (node (ref "TP5") (pin "1") (pinfunction "1_1") (pintype "passive"))
      (node (ref "U4") (pin "75") (pinfunction "PF26_75") (pintype "bidirectional"))
    )
    (net (code "30") (name "Net-(U4B-PF28)") (class "Default")
      (node (ref "TP9") (pin "1") (pinfunction "1_1") (pintype "passive"))
      (node (ref "U4") (pin "77") (pinfunction "PF28_77") (pintype "bidirectional"))
    )
    (net (code "31") (name "Net-(U4B-PF29)") (class "Default")
      (node (ref "TP6") (pin "1") (pinfunction "1_1") (pintype "passive"))
      (node (ref "U4") (pin "74") (pinfunction "PF29_74") (pintype "bidirectional"))
    )
    (net (code "32") (name "Net-(U4B-PF30{slash}VBUS_DET)") (class "Default")
      (node (ref "TP14") (pin "1") (pinfunction "1_1") (pintype "passive"))
      (node (ref "U4") (pin "2") (pinfunction "PF30/VBUS_DET_2") (pintype "bidirectional"))
    )
    (net (code "33") (name "Net-(U4B-PF31)") (class "Default")
      (node (ref "TP15") (pin "1") (pinfunction "1_1") (pintype "passive"))
      (node (ref "U4") (pin "3") (pinfunction "PF31_3") (pintype "bidirectional"))
    )
    (net (code "34") (name "Net-(U4D-ATEST)") (class "Default")
      (node (ref "TP12") (pin "1") (pinfunction "1_1") (pintype "passive"))
      (node (ref "U4") (pin "96") (pinfunction "ATEST_96") (pintype "passive"))
    )
    (net (code "35") (name "Net-(U4D-CFG_STRAP1)") (class "Default")
      (node (ref "R26") (pin "1") (pinfunction "1_1") (pintype "passive"))
      (node (ref "U4") (pin "21") (pinfunction "CFG_STRAP1_21") (pintype "input"))
    )
    (net (code "36") (name "Net-(U4D-CFG_STRAP2)") (class "Default")
      (node (ref "R30") (pin "2") (pinfunction "2_2") (pintype "passive"))
      (node (ref "U4") (pin "22") (pinfunction "CFG_STRAP2_22") (pintype "input"))
    )
    (net (code "37") (name "Net-(U4D-PF20{slash}CFG_NON_REM{slash}SPI_CE_N)") (class "Default")
      (node (ref "TP16") (pin "1") (pinfunction "1_1") (pintype "passive"))
      (node (ref "U4") (pin "69") (pinfunction "PF20/CFG_NON_REM/SPI_CE_N_69") (pintype "output"))
    )
    (net (code "38") (name "Net-(U4D-PF21{slash}SPI_CLK)") (class "Default")
      (node (ref "TP17") (pin "1") (pinfunction "1_1") (pintype "passive"))
      (node (ref "U4") (pin "68") (pinfunction "PF21/SPI_CLK_68") (pintype "output"))
    )
    (net (code "39") (name "Net-(U4D-PF22{slash}CFG_BC_EN{slash}SPI_D0)") (class "Default")
      (node (ref "TP11") (pin "1") (pinfunction "1_1") (pintype "passive"))
      (node (ref "U4") (pin "70") (pinfunction "PF22/CFG_BC_EN/SPI_D0_70") (pintype "bidirectional"))
    )
    (net (code "40") (name "Net-(U4D-PF23{slash}SPI_D1)") (class "Default")
      (node (ref "TP10") (pin "1") (pinfunction "1_1") (pintype "passive"))
      (node (ref "U4") (pin "71") (pinfunction "PF23/SPI_D1_71") (pintype "bidirectional"))
    )
    (net (code "41") (name "Net-(U4D-PF24{slash}SPI_D2)") (class "Default")
      (node (ref "TP8") (pin "1") (pinfunction "1_1") (pintype "passive"))
      (node (ref "U4") (pin "72") (pinfunction "PF24/SPI_D2_72") (pintype "bidirectional"))
    )
    (net (code "42") (name "Net-(U4D-PF25{slash}SPI_D3)") (class "Default")
      (node (ref "TP7") (pin "1") (pinfunction "1_1") (pintype "passive"))
      (node (ref "U4") (pin "73") (pinfunction "PF25/SPI_D3_73") (pintype "bidirectional"))
    )
    (net (code "43") (name "Net-(U4D-RBIAS)") (class "Default")
      (node (ref "R11") (pin "2") (pinfunction "2_2") (pintype "passive"))
      (node (ref "U4") (pin "100") (pinfunction "RBIAS_100") (pintype "passive"))
    )
    (net (code "44") (name "Net-(U4D-TEST1)") (class "Default")
      (node (ref "R23") (pin "2") (pinfunction "2_2") (pintype "passive"))
      (node (ref "U4") (pin "63") (pinfunction "TEST1_63") (pintype "input"))
    )
    (net (code "45") (name "Net-(U4D-TEST2)") (class "Default")
      (node (ref "R21") (pin "2") (pinfunction "2_2") (pintype "passive"))
      (node (ref "U4") (pin "64") (pinfunction "TEST2_64") (pintype "input"))
    )
    (net (code "46") (name "Net-(U4D-TEST3)") (class "Default")
      (node (ref "R16") (pin "2") (pinfunction "2_2") (pintype "passive"))
      (node (ref "U4") (pin "65") (pinfunction "TEST3_65") (pintype "input"))
    )
    (net (code "47") (name "Net-(U4D-TESTEN)") (class "Default")
      (node (ref "R31") (pin "2") (pinfunction "2_2") (pintype "passive"))
      (node (ref "U4") (pin "24") (pinfunction "TESTEN_24") (pintype "passive"))
    )
    (net (code "48") (name "Net-(U9-CT)") (class "Default")
      (node (ref "C61") (pin "2") (pinfunction "2_2") (pintype "passive"))
      (node (ref "U9") (pin "4") (pinfunction "CT_4") (pintype "passive"))
    )
    (net (code "49") (name "Net-(U10-FAULTn)") (class "Default")
      (node (ref "R52") (pin "2") (pinfunction "2_2") (pintype "passive"))
      (node (ref "U10") (pin "4") (pinfunction "FAULTn_4") (pintype "passive"))
    )
    (net (code "50") (name "Net-(U10-ILIM)") (class "Default")
      (node (ref "R55") (pin "1") (pinfunction "1_1") (pintype "passive"))
      (node (ref "U10") (pin "5") (pinfunction "ILIM_5") (pintype "passive"))
    )
    (net (code "51") (name "Net-(U11-FAULTn)") (class "Default")
      (node (ref "R51") (pin "2") (pinfunction "2_2") (pintype "passive"))
      (node (ref "U11") (pin "4") (pinfunction "FAULTn_4") (pintype "passive"))
    )
    (net (code "52") (name "Net-(U11-ILIM)") (class "Default")
      (node (ref "R57") (pin "1") (pinfunction "1_1") (pintype "passive"))
      (node (ref "U11") (pin "5") (pinfunction "ILIM_5") (pintype "passive"))
    )
    (net (code "53") (name "unconnected-(U4B-PF5-Pad46)") (class "Default")
      (node (ref "U4") (pin "46") (pinfunction "PF5_46") (pintype "bidirectional+no_connect"))
    )
    (net (code "54") (name "unconnected-(U4B-PF8-Pad49)") (class "Default")
      (node (ref "U4") (pin "49") (pinfunction "PF8_49") (pintype "bidirectional+no_connect"))
    )
    (net (code "55") (name "unconnected-(U4B-PF9-Pad50)") (class "Default")
      (node (ref "U4") (pin "50") (pinfunction "PF9_50") (pintype "bidirectional+no_connect"))
    )
    (net (code "56") (name "unconnected-(U4B-PF17-Pad60)") (class "Default")
      (node (ref "U4") (pin "60") (pinfunction "PF17_60") (pintype "bidirectional+no_connect"))
    )
    (net (code "57") (name "unconnected-(U4D-CFG_STRAP3-Pad23)") (class "Default")
      (node (ref "U4") (pin "23") (pinfunction "CFG_STRAP3_23") (pintype "input+no_connect"))
    )
    (net (code "58") (name "unconnected-(X1-Pad2)") (class "Default")
      (node (ref "X1") (pin "2") (pinfunction "2_2") (pintype "passive+no_connect"))
    )
    (net (code "59") (name "unconnected-(X1-Pad4)") (class "Default")
      (node (ref "X1") (pin "4") (pinfunction "4_4") (pintype "passive+no_connect"))
    )
  )
)
